# Sensor_Board.net
KiCad netlist of a schematic drawn in Altium Designer
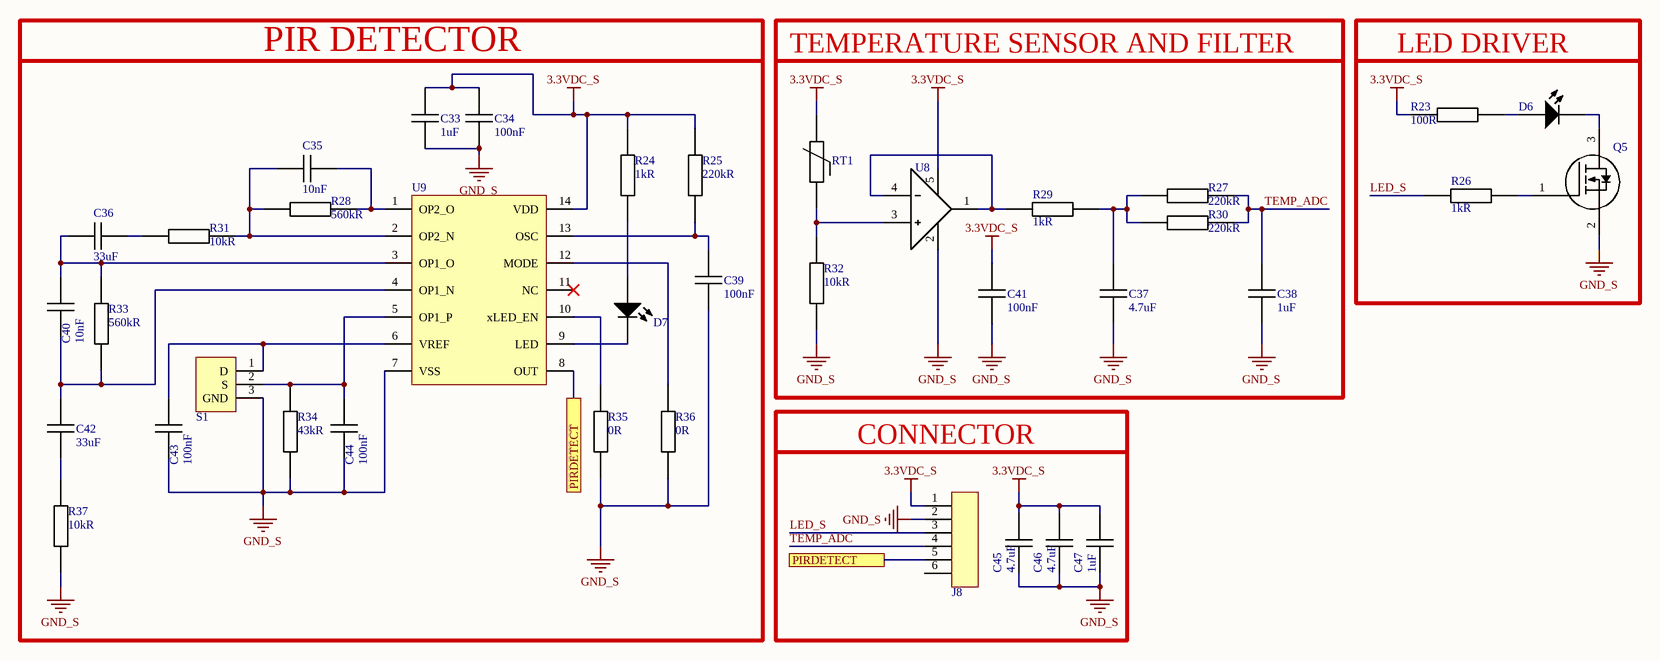
[diagram p0: Sensor Board.SchDoc]

(export (version "E")
  (design (tool "Eeschema 10.0.6"))
  (components
    (comp (ref "C33")
      (value "1uF")
      (footprint "CAP_0805")
      (description "Multilayer Ceramic Capacitor, 1 uF, 50 V, 10%, X7R, 0805 [2012 Metric]")
      (fields
        (field (name "MANUFACTURER") "Samsung")
        (field (name "MANUFACTURER PART NUMBER") "CL21B105KBFNNNE")
        (field (name "DESIGNED BY") "FURKAN")
      )
      (libsource (lib "Udemy_Library") (part "CAP CER 1uF 0805"))
    )
    (comp (ref "C34")
      (value "100nF")
      (footprint "CAP_0805")
      (description "CAP CER 100 nF 10% 50 V 0805 SMD")
      (fields
        (field (name "MANUFACTURER") "Samsung")
        (field (name "MANUFACTURER PART NUMBER") "CL21B104KBCNNNC")
        (field (name "DESIGNED BY") "FURKAN")
      )
      (libsource (lib "Udemy_Library") (part "CAP CER 100nF 0805"))
    )
    (comp (ref "C35")
      (value "10nF")
      (footprint "CAP_0603")
      (description "CAP CER 10nF 10% 16V 0603 SMD")
      (fields
        (field (name "MANUFACTURER") "Walsin Technologies")
        (field (name "MANUFACTURER PART NUMBER") "0603B103K160CT")
        (field (name "DESIGNED BY") "FURKAN")
      )
      (libsource (lib "Udemy_Library") (part "CAP CER 10nF 0603"))
    )
    (comp (ref "C36")
      (value "33uF")
      (footprint "CAP_1206")
      (description "CAP CER 33 uF ± 20% 25 V 1206 SMD")
      (fields
        (field (name "MANUFACTURER") "TDK")
        (field (name "MANUFACTURER PART NUMBER") "C3216X5R1E336M160AC")
        (field (name "DESIGNED BY") "FURKAN")
      )
      (libsource (lib "Udemy_Library") (part "CAP CER 33uF 1206"))
    )
    (comp (ref "C37")
      (value "4.7uF")
      (footprint "CAP_0805")
      (description "Multilayer Ceramic Capacitor, 4.7 uF, 25 V, ± 10%, X5R, 0805 [2012 Metric]")
      (fields
        (field (name "MANUFACTURER") "Samsung")
        (field (name "MANUFACTURER PART NUMBER") "CL21A475KAQNNNE")
        (field (name "DESIGNED BY") "FURKAN")
      )
      (libsource (lib "Udemy_Library") (part "CAP CER 4.7uF 0805"))
    )
    (comp (ref "C38")
      (value "1uF")
      (footprint "CAP_0805")
      (description "Multilayer Ceramic Capacitor, 1 uF, 50 V, 10%, X7R, 0805 [2012 Metric]")
      (fields
        (field (name "MANUFACTURER") "Samsung")
        (field (name "MANUFACTURER PART NUMBER") "CL21B105KBFNNNE")
        (field (name "DESIGNED BY") "FURKAN")
      )
      (libsource (lib "Udemy_Library") (part "CAP CER 1uF 0805"))
    )
    (comp (ref "C39")
      (value "100nF")
      (footprint "CAP_0603")
      (description "CAP CER 100 nF %20 0603 SMD")
      (fields
        (field (name "MANUFACTURER") "KEMET")
        (field (name "MANUFACTURER PART NUMBER") "C0603C104M5RACTU")
        (field (name "DESIGNED BY") "FURKAN")
      )
      (libsource (lib "Udemy_Library") (part "CAP CER 100nF 0603"))
    )
    (comp (ref "C40")
      (value "10nF")
      (footprint "CAP_0603")
      (description "CAP CER 10nF 10% 16V 0603 SMD")
      (fields
        (field (name "MANUFACTURER") "Walsin Technologies")
        (field (name "MANUFACTURER PART NUMBER") "0603B103K160CT")
        (field (name "DESIGNED BY") "FURKAN")
      )
      (libsource (lib "Udemy_Library") (part "CAP CER 10nF 0603"))
    )
    (comp (ref "C41")
      (value "100nF")
      (footprint "CAP_0603")
      (description "CAP CER 100 nF %20 0603 SMD")
      (fields
        (field (name "MANUFACTURER") "KEMET")
        (field (name "MANUFACTURER PART NUMBER") "C0603C104M5RACTU")
        (field (name "DESIGNED BY") "FURKAN")
      )
      (libsource (lib "Udemy_Library") (part "CAP CER 100nF 0603"))
    )
    (comp (ref "C42")
      (value "33uF")
      (footprint "CAP_1206")
      (description "CAP CER 33 uF ± 20% 25 V 1206 SMD")
      (fields
        (field (name "MANUFACTURER") "TDK")
        (field (name "MANUFACTURER PART NUMBER") "C3216X5R1E336M160AC")
        (field (name "DESIGNED BY") "FURKAN")
      )
      (libsource (lib "Udemy_Library") (part "CAP CER 33uF 1206"))
    )
    (comp (ref "C43")
      (value "100nF")
      (footprint "CAP_0603")
      (description "CAP CER 100 nF %20 0603 SMD")
      (fields
        (field (name "MANUFACTURER") "KEMET")
        (field (name "MANUFACTURER PART NUMBER") "C0603C104M5RACTU")
        (field (name "DESIGNED BY") "FURKAN")
      )
      (libsource (lib "Udemy_Library") (part "CAP CER 100nF 0603"))
    )
    (comp (ref "C44")
      (value "100nF")
      (footprint "CAP_0603")
      (description "CAP CER 100 nF %20 0603 SMD")
      (fields
        (field (name "MANUFACTURER") "KEMET")
        (field (name "MANUFACTURER PART NUMBER") "C0603C104M5RACTU")
        (field (name "DESIGNED BY") "FURKAN")
      )
      (libsource (lib "Udemy_Library") (part "CAP CER 100nF 0603"))
    )
    (comp (ref "C45")
      (value "4.7uF")
      (footprint "CAP_0805")
      (description "Multilayer Ceramic Capacitor, 4.7 uF, 25 V, ± 10%, X5R, 0805 [2012 Metric]")
      (fields
        (field (name "MANUFACTURER") "Samsung")
        (field (name "MANUFACTURER PART NUMBER") "CL21A475KAQNNNE")
        (field (name "DESIGNED BY") "FURKAN")
      )
      (libsource (lib "Udemy_Library") (part "CAP CER 4.7uF 0805"))
    )
    (comp (ref "C46")
      (value "4.7uF")
      (footprint "CAP_0805")
      (description "Multilayer Ceramic Capacitor, 4.7 uF, 25 V, ± 10%, X5R, 0805 [2012 Metric]")
      (fields
        (field (name "MANUFACTURER") "Samsung")
        (field (name "MANUFACTURER PART NUMBER") "CL21A475KAQNNNE")
        (field (name "DESIGNED BY") "FURKAN")
      )
      (libsource (lib "Udemy_Library") (part "CAP CER 4.7uF 0805"))
    )
    (comp (ref "C47")
      (value "1uF")
      (footprint "CAP_0805")
      (description "Multilayer Ceramic Capacitor, 1 uF, 50 V, 10%, X7R, 0805 [2012 Metric]")
      (fields
        (field (name "MANUFACTURER") "Samsung")
        (field (name "MANUFACTURER PART NUMBER") "CL21B105KBFNNNE")
        (field (name "DESIGNED BY") "FURKAN")
      )
      (libsource (lib "Udemy_Library") (part "CAP CER 1uF 0805"))
    )
    (comp (ref "D6")
      (value "LTST-C171KRKT")
      (footprint "LED_RED_0805")
      (description "LED Uni-Color Red 639nm 2-Pin Chip LED T/R")
      (fields (field (name "MANUFACTURER") "Vishay Lite-On") (field (name "DESIGNED BY") "FURKAN"))
      (libsource (lib "Udemy_Library") (part "LED RED 0805"))
    )
    (comp (ref "D7")
      (value "LTST-C171GKT")
      (footprint "LED_GREEN_0805")
      (description "LED Low-Power Uni-Color Green 565nm 2.1V 2-Pin Chip LED T/R")
      (fields (field (name "MANUFACTURER") "Vishay Lite-On") (field (name "DESIGNED BY") "FURKAN"))
      (libsource (lib "Udemy_Library") (part "LED GREEN 0805"))
    )
    (comp (ref "J8")
      (value "64800611622")
      (footprint "64800611622")
      (description "WR-WTB Wire-to-Board Connectors 1.50 mm 6-Pin Connector")
      (fields (field (name "MANUFACTURER") "Wurth Electronics") (field (name "DESIGNED BY") "FURKAN"))
      (libsource (lib "Udemy_Library") (part "64800611622_Conn_6Pin"))
    )
    (comp (ref "Q5")
      (value "SSM3K357R,LF")
      (footprint "SOT23F")
      (description "Trans MOSFET N-CH Si 60V 0.65A Automotive 3-Pin SOT-23F T/R")
      (fields (field (name "MANUFACTURER") "Toshiba") (field (name "DESIGNED BY") "FURKAN"))
      (libsource (lib "Udemy_Library") (part "SSM3K357R,LF"))
    )
    (comp (ref "R23")
      (value "100R")
      (footprint "RES_0603")
      (description "RES 100 OHM 1% 0603 SMD")
      (fields
        (field (name "MANUFACTURER") "Yageo")
        (field (name "MANUFACTURER PART NUMBER") "RC0603FR-07100RL")
        (field (name "DESIGNED BY") "FURKAN")
      )
      (libsource (lib "Udemy_Library") (part "RES 100 OHM 0603"))
    )
    (comp (ref "R24")
      (value "1kR")
      (footprint "RES_0603")
      (description "RES 1K OHM 1% 0603 SMD")
      (fields
        (field (name "MANUFACTURER") "Yageo")
        (field (name "MANUFACTURER PART NUMBER") "RC0603FR-071KL")
        (field (name "DESIGNED BY") "FURKAN")
      )
      (libsource (lib "Udemy_Library") (part "RES 1K OHM 0603"))
    )
    (comp (ref "R25")
      (value "220kR")
      (footprint "RES_0603")
      (description "RES 220K OHM 5% 0603 SMD")
      (fields
        (field (name "MANUFACTURER") "Yageo")
        (field (name "MANUFACTURER PART NUMBER") "RC0603JR-07220KL")
        (field (name "DESIGNED BY") "FURKAN")
      )
      (libsource (lib "") (part "RES 220K OHM 0603_1"))
    )
    (comp (ref "R26")
      (value "1kR")
      (footprint "RES_0603")
      (description "RES 1K OHM 1% 0603 SMD")
      (fields
        (field (name "MANUFACTURER") "Yageo")
        (field (name "MANUFACTURER PART NUMBER") "RC0603FR-071KL")
        (field (name "DESIGNED BY") "FURKAN")
      )
      (libsource (lib "") (part "RES 1K OHM 0603_1"))
    )
    (comp (ref "R27")
      (value "220kR")
      (footprint "RES_0603")
      (description "RES 220K OHM 5% 0603 SMD")
      (fields
        (field (name "MANUFACTURER") "Yageo")
        (field (name "MANUFACTURER PART NUMBER") "RC0603JR-07220KL")
        (field (name "DESIGNED BY") "FURKAN")
      )
      (libsource (lib "Udemy_Library") (part "RES 220K OHM 0603"))
    )
    (comp (ref "R28")
      (value "560kR")
      (footprint "RES_0603")
      (description "RES 560K OHM 5% 0603 SMD")
      (fields
        (field (name "MANUFACTURER") "Yageo")
        (field (name "MANUFACTURER PART NUMBER") "RC0603JR-07560KL")
        (field (name "DESIGNED BY") "FURKAN")
      )
      (libsource (lib "") (part "RES 560K OHM 0603_1"))
    )
    (comp (ref "R29")
      (value "1kR")
      (footprint "RES_0603")
      (description "RES 1K OHM 1% 0603 SMD")
      (fields
        (field (name "MANUFACTURER") "Yageo")
        (field (name "MANUFACTURER PART NUMBER") "RC0603FR-071KL")
        (field (name "DESIGNED BY") "FURKAN")
      )
      (libsource (lib "") (part "RES 1K OHM 0603_1"))
    )
    (comp (ref "R30")
      (value "220kR")
      (footprint "RES_0603")
      (description "RES 220K OHM 5% 0603 SMD")
      (fields
        (field (name "MANUFACTURER") "Yageo")
        (field (name "MANUFACTURER PART NUMBER") "RC0603JR-07220KL")
        (field (name "DESIGNED BY") "FURKAN")
      )
      (libsource (lib "Udemy_Library") (part "RES 220K OHM 0603"))
    )
    (comp (ref "R31")
      (value "10kR")
      (footprint "RES_0603")
      (description "RES 10K OHM %1 0603 SMD")
      (fields
        (field (name "MANUFACTURER") "Yageo")
        (field (name "MANUFACTURER PART NUMBER") "RC0603FR-0710KL")
        (field (name "DESIGNED BY") "FURKAN")
      )
      (libsource (lib "") (part "RES 10K OHM 0603_1"))
    )
    (comp (ref "R32")
      (value "10kR")
      (footprint "RES_0603")
      (description "RES 10K OHM %1 0603 SMD")
      (fields
        (field (name "MANUFACTURER") "Yageo")
        (field (name "MANUFACTURER PART NUMBER") "RC0603FR-0710KL")
        (field (name "DESIGNED BY") "FURKAN")
      )
      (libsource (lib "Udemy_Library") (part "RES 10K OHM 0603"))
    )
    (comp (ref "R33")
      (value "560kR")
      (footprint "RES_0603")
      (description "RES 560K OHM 5% 0603 SMD")
      (fields
        (field (name "MANUFACTURER") "Yageo")
        (field (name "MANUFACTURER PART NUMBER") "RC0603JR-07560KL")
        (field (name "DESIGNED BY") "FURKAN")
      )
      (libsource (lib "Udemy_Library") (part "RES 560K OHM 0603"))
    )
    (comp (ref "R34")
      (value "43kR")
      (footprint "RES_0603")
      (description "RES 43K OHM 5% 0603 SMD")
      (fields
        (field (name "MANUFACTURER") "Yageo")
        (field (name "MANUFACTURER PART NUMBER") "RC0603JR-0743KL")
        (field (name "DESIGNED BY") "FURKAN")
      )
      (libsource (lib "Udemy_Library") (part "RES 43K OHM 0603"))
    )
    (comp (ref "R35")
      (value "0R")
      (footprint "RES_0603")
      (description "RES 0 OHM 1% 0603 SMD")
      (fields
        (field (name "MANUFACTURER") "Yageo")
        (field (name "MANUFACTURER PART NUMBER") "RC0603JR-070RL")
        (field (name "DESIGNED BY") "FURKAN")
      )
      (libsource (lib "Udemy_Library") (part "RES 0 OHM 0603"))
    )
    (comp (ref "R36")
      (value "0R")
      (footprint "RES_0603")
      (description "RES 0 OHM 1% 0603 SMD")
      (fields
        (field (name "MANUFACTURER") "Yageo")
        (field (name "MANUFACTURER PART NUMBER") "RC0603JR-070RL")
        (field (name "DESIGNED BY") "FURKAN")
      )
      (libsource (lib "Udemy_Library") (part "RES 0 OHM 0603"))
    )
    (comp (ref "R37")
      (value "10kR")
      (footprint "RES_0603")
      (description "RES 10K OHM %1 0603 SMD")
      (fields
        (field (name "MANUFACTURER") "Yageo")
        (field (name "MANUFACTURER PART NUMBER") "RC0603FR-0710KL")
        (field (name "DESIGNED BY") "FURKAN")
      )
      (libsource (lib "Udemy_Library") (part "RES 10K OHM 0603"))
    )
    (comp (ref "RT1")
      (value "TFPT1206L1002FM")
      (footprint "RT_1206")
      (description "Thermistor PTC 10K Ohm 1% 2-Pin 1206 Surface Mount Solder Pad T/R Automotive")
      (fields
        (field (name "MANUFACTURER") "Vishay Dale")
        (field (name "TOLERANCE") "1%")
        (field (name "DESIGNED BY") "FURKAN")
      )
      (libsource (lib "Udemy_Library") (part "TFPT1206L1002FM"))
    )
    (comp (ref "S1")
      (value "LHI 878/3902")
      (footprint "LHI 878")
      (description "Sensor Pyro Detector Dual Motion")
      (fields
        (field (name "MANUFACTURER") "Excelitas")
        (field (name "MANUFACTURER PART NUMBER") "LHI878/3902")
        (field (name "DESIGNED BY") "FURKAN")
      )
      (libsource (lib "Udemy_Library") (part "LHI 878/3902"))
    )
    (comp (ref "U8")
      (value "OPA314AIDBVR")
      (footprint "SOT23-5")
      (description "IC OPAMP GP 3MHZ RRO SOT23-5")
      (fields (field (name "MANUFACTURER") "Texas Instruments") (field (name "DESIGNED BY") "FURKAN"))
      (libsource (lib "Udemy_Library") (part "OPA314"))
    )
    (comp (ref "U9")
      (value "NCS36000DRG")
      (footprint "SOIC14")
      (description "PIR Controller NCS36000 Series Single 5.75V SOIC-14")
      (fields (field (name "MANUFACTURER") "ON Semiconductor") (field (name "DESIGNED BY") "FURKAN"))
      (libsource (lib "Udemy_Library") (part "NCS36000"))
    )
  )
  (nets
    (net (code "1") (name "/LED_S") (class "Default")
      (node (ref "J8") (pin "3") (pintype "passive"))
      (node (ref "R26") (pin "1") (pinfunction "1_1") (pintype "passive"))
    )
    (net (code "2") (name "/PIRDETECT") (class "Default")
      (node (ref "J8") (pin "5") (pintype "passive"))
      (node (ref "U9") (pin "8") (pinfunction "OUT_8") (pintype "passive"))
    )
    (net (code "3") (name "/TEMP_ADC") (class "Default")
      (node (ref "C38") (pin "1") (pinfunction "1_1") (pintype "passive"))
      (node (ref "J8") (pin "4") (pintype "passive"))
      (node (ref "R27") (pin "2") (pinfunction "2_2") (pintype "passive"))
      (node (ref "R30") (pin "2") (pinfunction "2_2") (pintype "passive"))
    )
    (net (code "4") (name "3.3VDC_S") (class "Default")
      (node (ref "C33") (pin "2") (pinfunction "2_2") (pintype "passive"))
      (node (ref "C34") (pin "1") (pinfunction "1_1") (pintype "passive"))
      (node (ref "C41") (pin "1") (pinfunction "1_1") (pintype "passive"))
      (node (ref "C45") (pin "2") (pinfunction "2_2") (pintype "passive"))
      (node (ref "C46") (pin "2") (pinfunction "2_2") (pintype "passive"))
      (node (ref "C47") (pin "2") (pinfunction "2_2") (pintype "passive"))
      (node (ref "J8") (pin "1") (pintype "passive"))
      (node (ref "R23") (pin "1") (pinfunction "1_1") (pintype "passive"))
      (node (ref "R24") (pin "1") (pinfunction "1_1") (pintype "passive"))
      (node (ref "R25") (pin "1") (pinfunction "1_1") (pintype "passive"))
      (node (ref "RT1") (pin "1") (pinfunction "1_1") (pintype "passive"))
      (node (ref "U8") (pin "5") (pinfunction "V+_5") (pintype "passive"))
      (node (ref "U9") (pin "14") (pinfunction "VDD_14") (pintype "passive"))
    )
    (net (code "5") (name "GND_S") (class "Default")
      (node (ref "C33") (pin "1") (pinfunction "1_1") (pintype "passive"))
      (node (ref "C34") (pin "2") (pinfunction "2_2") (pintype "passive"))
      (node (ref "C37") (pin "1") (pinfunction "1_1") (pintype "passive"))
      (node (ref "C38") (pin "2") (pinfunction "2_2") (pintype "passive"))
      (node (ref "C39") (pin "2") (pinfunction "2_2") (pintype "passive"))
      (node (ref "C41") (pin "2") (pinfunction "2_2") (pintype "passive"))
      (node (ref "C43") (pin "2") (pinfunction "2_2") (pintype "passive"))
      (node (ref "C44") (pin "2") (pinfunction "2_2") (pintype "passive"))
      (node (ref "C45") (pin "1") (pinfunction "1_1") (pintype "passive"))
      (node (ref "C46") (pin "1") (pinfunction "1_1") (pintype "passive"))
      (node (ref "C47") (pin "1") (pinfunction "1_1") (pintype "passive"))
      (node (ref "J8") (pin "2") (pintype "passive"))
      (node (ref "Q5") (pin "2") (pinfunction "S_2") (pintype "passive"))
      (node (ref "R32") (pin "1") (pinfunction "1_1") (pintype "passive"))
      (node (ref "R34") (pin "2") (pinfunction "2_2") (pintype "passive"))
      (node (ref "R35") (pin "2") (pinfunction "2_2") (pintype "passive"))
      (node (ref "R36") (pin "2") (pinfunction "2_2") (pintype "passive"))
      (node (ref "R37") (pin "1") (pinfunction "1_1") (pintype "passive"))
      (node (ref "S1") (pin "3") (pinfunction "GND_3") (pintype "passive"))
      (node (ref "U8") (pin "2") (pinfunction "V-_2") (pintype "passive"))
      (node (ref "U9") (pin "7") (pinfunction "VSS_7") (pintype "passive"))
    )
    (net (code "6") (name "Net-(C36-Pad1)") (class "Default")
      (node (ref "C36") (pin "1") (pinfunction "1_1") (pintype "passive"))
      (node (ref "R31") (pin "1") (pinfunction "1_1") (pintype "passive"))
    )
    (net (code "7") (name "Net-(C37-Pad2)") (class "Default")
      (node (ref "C37") (pin "2") (pinfunction "2_2") (pintype "passive"))
      (node (ref "R27") (pin "1") (pinfunction "1_1") (pintype "passive"))
      (node (ref "R29") (pin "2") (pinfunction "2_2") (pintype "passive"))
      (node (ref "R30") (pin "1") (pinfunction "1_1") (pintype "passive"))
    )
    (net (code "8") (name "Net-(C42-Pad2)") (class "Default")
      (node (ref "C42") (pin "2") (pinfunction "2_2") (pintype "passive"))
      (node (ref "R37") (pin "2") (pinfunction "2_2") (pintype "passive"))
    )
    (net (code "9") (name "Net-(D6-Pad1)") (class "Default")
      (node (ref "D6") (pin "1") (pinfunction "1_1") (pintype "passive"))
      (node (ref "R23") (pin "2") (pinfunction "2_2") (pintype "passive"))
    )
    (net (code "10") (name "Net-(D7-Pad1)") (class "Default")
      (node (ref "D7") (pin "1") (pinfunction "1_1") (pintype "passive"))
      (node (ref "R24") (pin "2") (pinfunction "2_2") (pintype "passive"))
    )
    (net (code "11") (name "Net-(Q5-D)") (class "Default")
      (node (ref "D6") (pin "2") (pinfunction "2_2") (pintype "passive"))
      (node (ref "Q5") (pin "3") (pinfunction "D_3") (pintype "passive"))
    )
    (net (code "12") (name "Net-(Q5-G)") (class "Default")
      (node (ref "Q5") (pin "1") (pinfunction "G_1") (pintype "passive"))
      (node (ref "R26") (pin "2") (pinfunction "2_2") (pintype "passive"))
    )
    (net (code "13") (name "Net-(S1-D)") (class "Default")
      (node (ref "C43") (pin "1") (pinfunction "1_1") (pintype "passive"))
      (node (ref "S1") (pin "1") (pinfunction "D_1") (pintype "passive"))
      (node (ref "U9") (pin "6") (pinfunction "VREF_6") (pintype "passive"))
    )
    (net (code "14") (name "Net-(S1-S)") (class "Default")
      (node (ref "C44") (pin "1") (pinfunction "1_1") (pintype "passive"))
      (node (ref "R34") (pin "1") (pinfunction "1_1") (pintype "passive"))
      (node (ref "S1") (pin "2") (pinfunction "S_2") (pintype "passive"))
      (node (ref "U9") (pin "5") (pinfunction "OP1_P_5") (pintype "passive"))
    )
    (net (code "15") (name "Net-(U8-IN+)") (class "Default")
      (node (ref "R32") (pin "2") (pinfunction "2_2") (pintype "passive"))
      (node (ref "RT1") (pin "2") (pinfunction "2_2") (pintype "passive"))
      (node (ref "U8") (pin "3") (pinfunction "IN+_3") (pintype "passive"))
    )
    (net (code "16") (name "Net-(U8-IN-)") (class "Default")
      (node (ref "R29") (pin "1") (pinfunction "1_1") (pintype "passive"))
      (node (ref "U8") (pin "1") (pinfunction "OUT_1") (pintype "passive"))
      (node (ref "U8") (pin "4") (pinfunction "IN-_4") (pintype "passive"))
    )
    (net (code "17") (name "Net-(U9-LED)") (class "Default")
      (node (ref "D7") (pin "2") (pinfunction "2_2") (pintype "passive"))
      (node (ref "U9") (pin "9") (pinfunction "LED_9") (pintype "passive"))
    )
    (net (code "18") (name "Net-(U9-MODE)") (class "Default")
      (node (ref "R36") (pin "1") (pinfunction "1_1") (pintype "passive"))
      (node (ref "U9") (pin "12") (pinfunction "MODE_12") (pintype "passive"))
    )
    (net (code "19") (name "Net-(U9-OP1_N)") (class "Default")
      (node (ref "C40") (pin "1") (pinfunction "1_1") (pintype "passive"))
      (node (ref "C42") (pin "1") (pinfunction "1_1") (pintype "passive"))
      (node (ref "R33") (pin "2") (pinfunction "2_2") (pintype "passive"))
      (node (ref "U9") (pin "4") (pinfunction "OP1_N_4") (pintype "passive"))
    )
    (net (code "20") (name "Net-(U9-OP1_O)") (class "Default")
      (node (ref "C36") (pin "2") (pinfunction "2_2") (pintype "passive"))
      (node (ref "C40") (pin "2") (pinfunction "2_2") (pintype "passive"))
      (node (ref "R33") (pin "1") (pinfunction "1_1") (pintype "passive"))
      (node (ref "U9") (pin "3") (pinfunction "OP1_O_3") (pintype "passive"))
    )
    (net (code "21") (name "Net-(U9-OP2_N)") (class "Default")
      (node (ref "C35") (pin "2") (pinfunction "2_2") (pintype "passive"))
      (node (ref "R28") (pin "1") (pinfunction "1_1") (pintype "passive"))
      (node (ref "R31") (pin "2") (pinfunction "2_2") (pintype "passive"))
      (node (ref "U9") (pin "2") (pinfunction "OP2_N_2") (pintype "passive"))
    )
    (net (code "22") (name "Net-(U9-OP2_O)") (class "Default")
      (node (ref "C35") (pin "1") (pinfunction "1_1") (pintype "passive"))
      (node (ref "R28") (pin "2") (pinfunction "2_2") (pintype "passive"))
      (node (ref "U9") (pin "1") (pinfunction "OP2_O_1") (pintype "passive"))
    )
    (net (code "23") (name "Net-(U9-OSC)") (class "Default")
      (node (ref "C39") (pin "1") (pinfunction "1_1") (pintype "passive"))
      (node (ref "R25") (pin "2") (pinfunction "2_2") (pintype "passive"))
      (node (ref "U9") (pin "13") (pinfunction "OSC_13") (pintype "passive"))
    )
    (net (code "24") (name "Net-(U9-xLED_EN)") (class "Default")
      (node (ref "R35") (pin "1") (pinfunction "1_1") (pintype "passive"))
      (node (ref "U9") (pin "10") (pinfunction "xLED_EN_10") (pintype "passive"))
    )
    (net (code "25") (name "unconnected-(J8-Pad6)") (class "Default")
      (node (ref "J8") (pin "6") (pintype "passive"))
    )
    (net (code "26") (name "unconnected-(U9-NC-Pad11)") (class "Default")
      (node (ref "U9") (pin "11") (pinfunction "NC_11") (pintype "passive+no_connect"))
    )
  )
)
